# rfid_module_v4.net
KiCad netlist of a schematic drawn in EAGLE
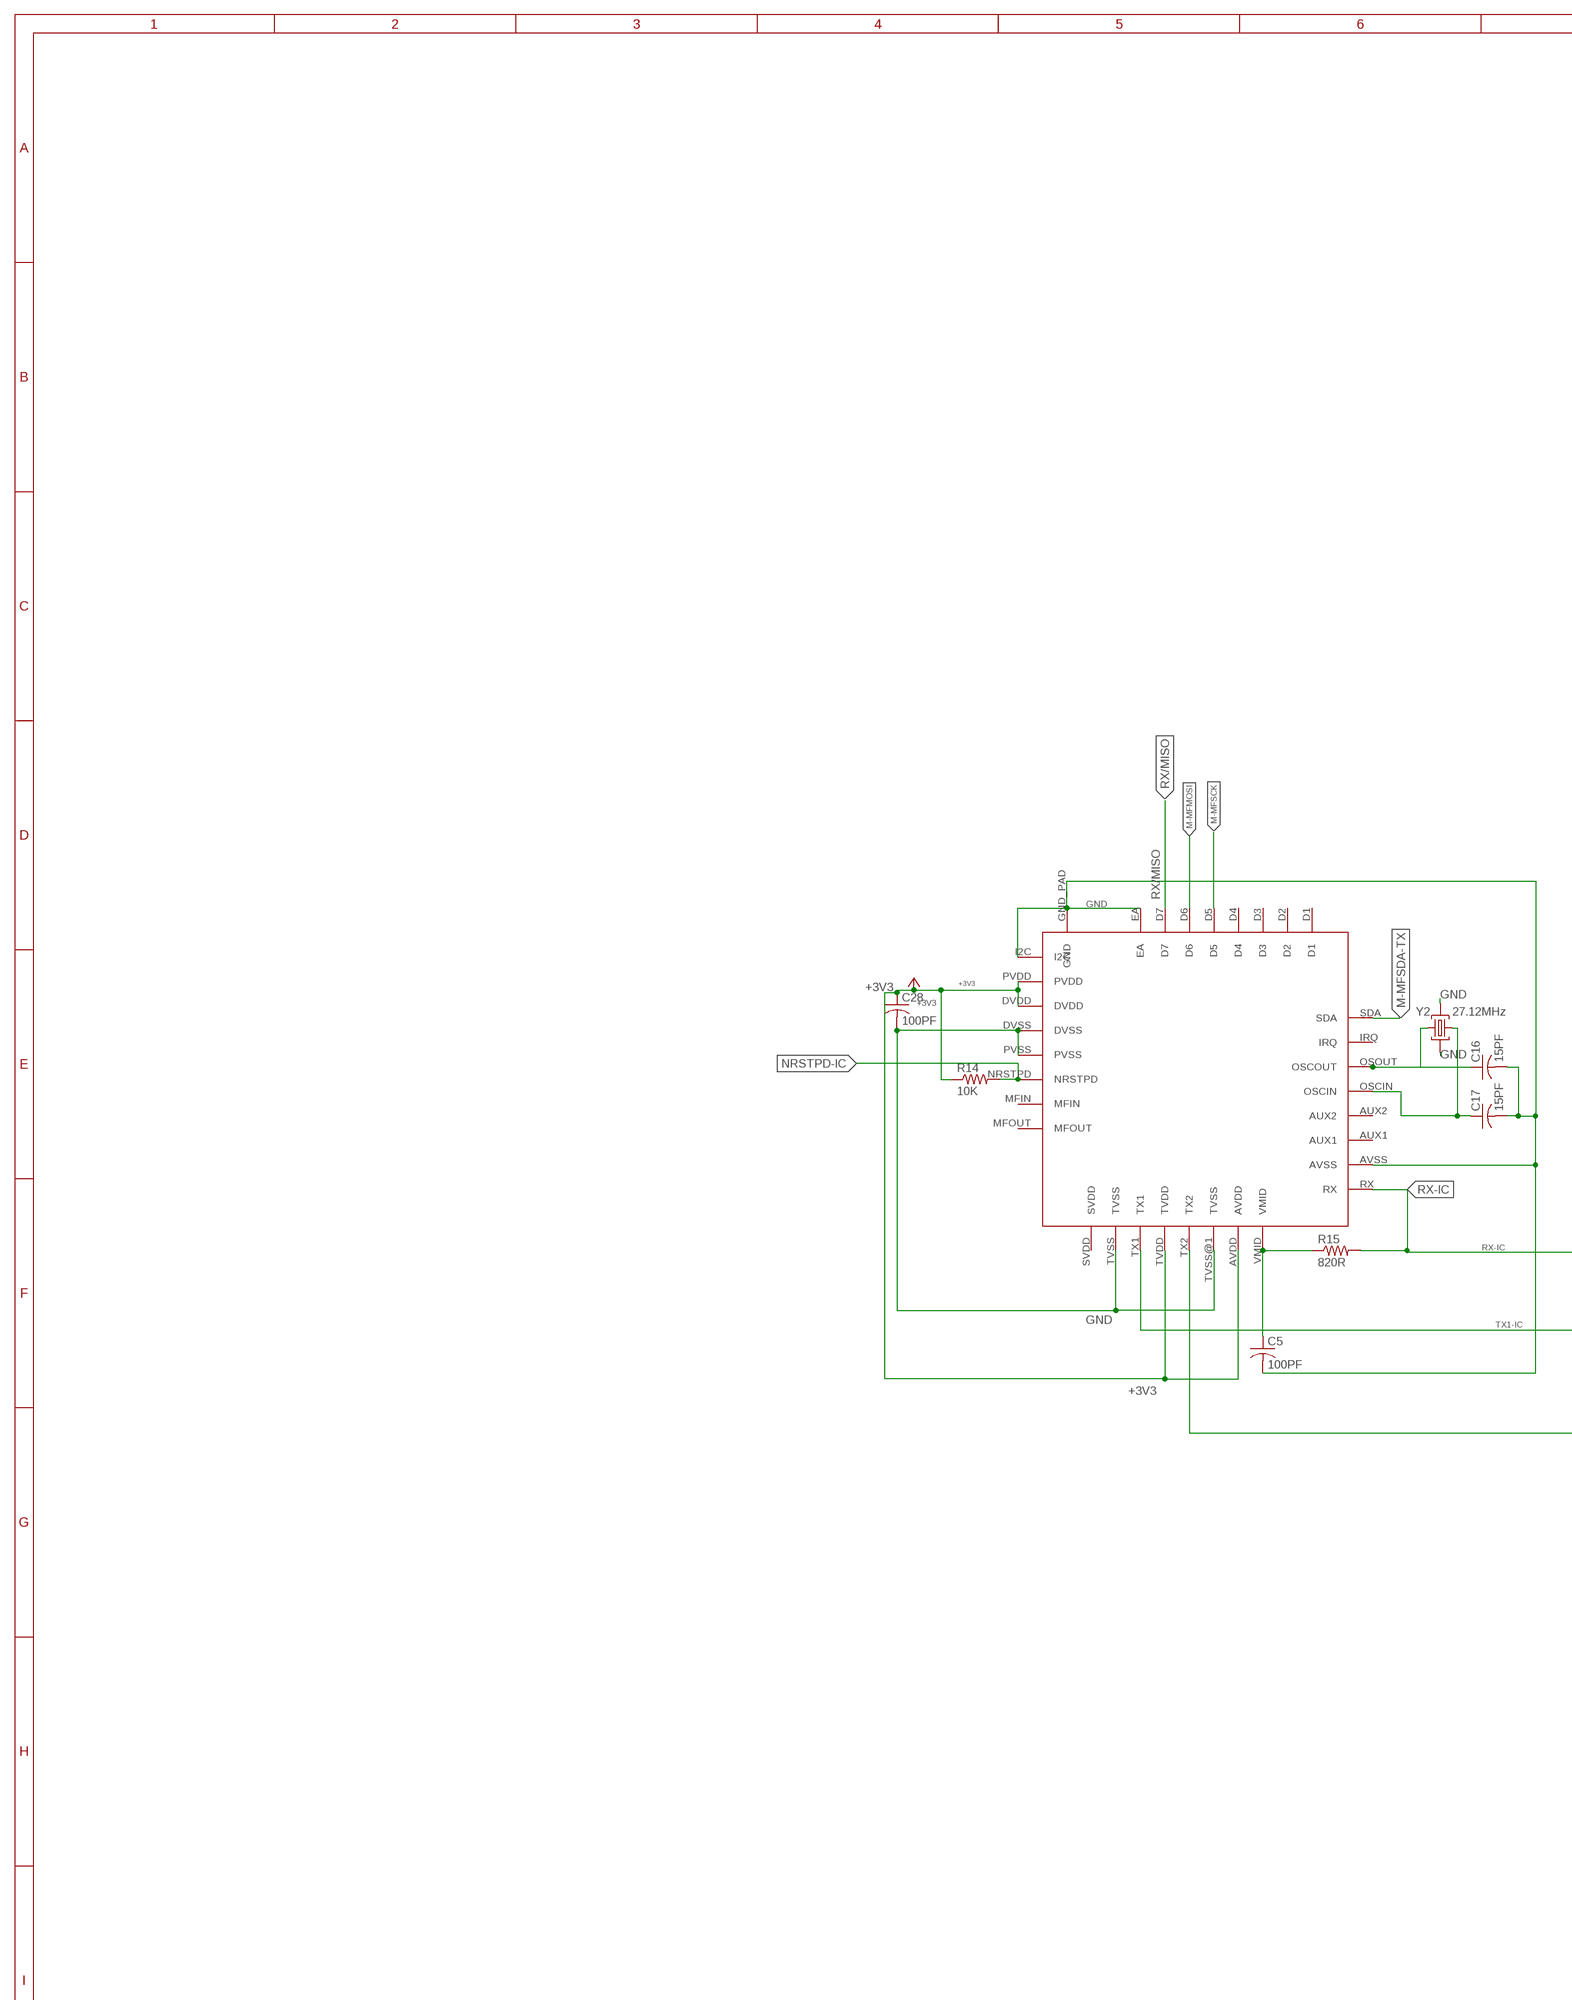
[diagram p0: schematic, sheet 1, part 1 of 2]
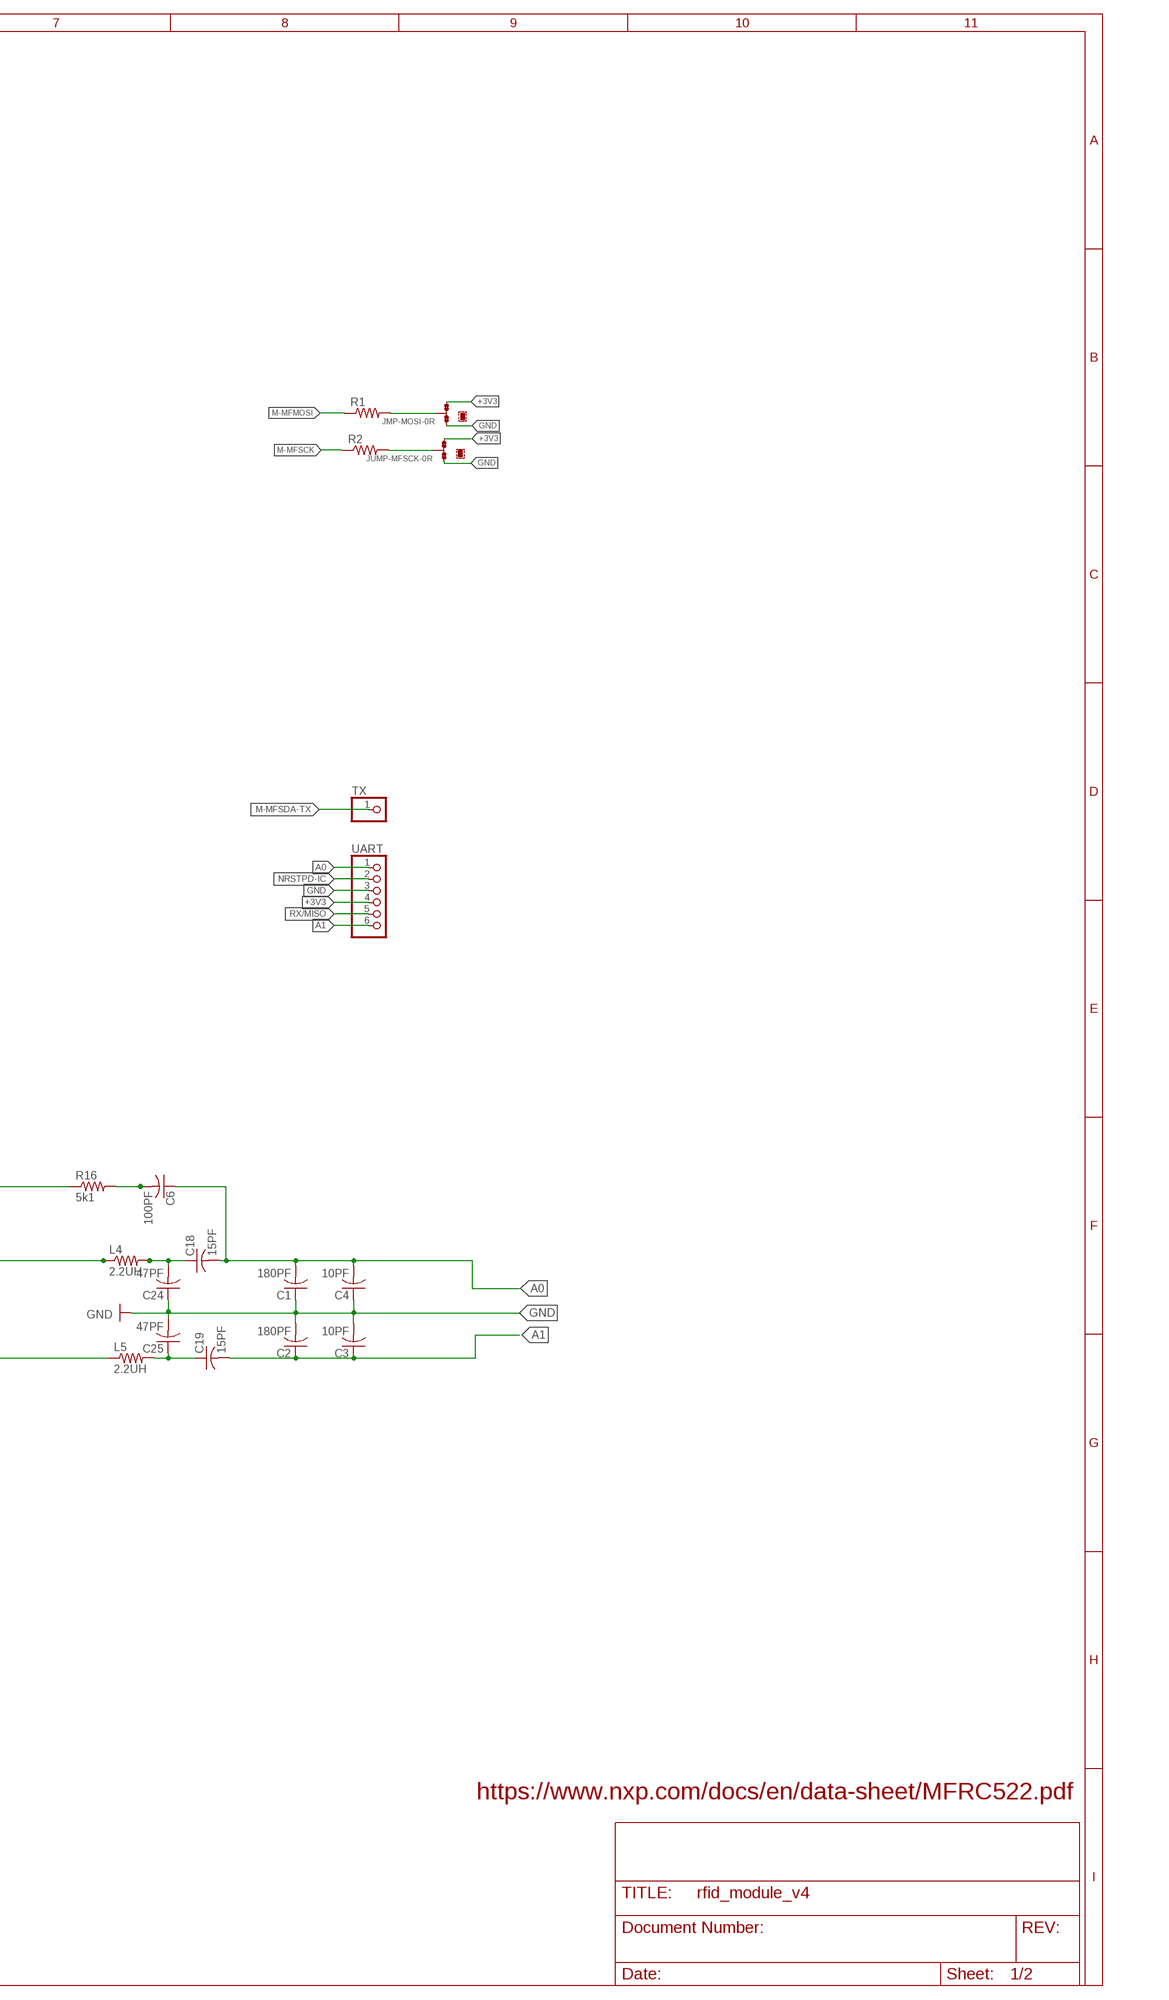
[diagram p1: schematic, sheet 1, part 2 of 2]
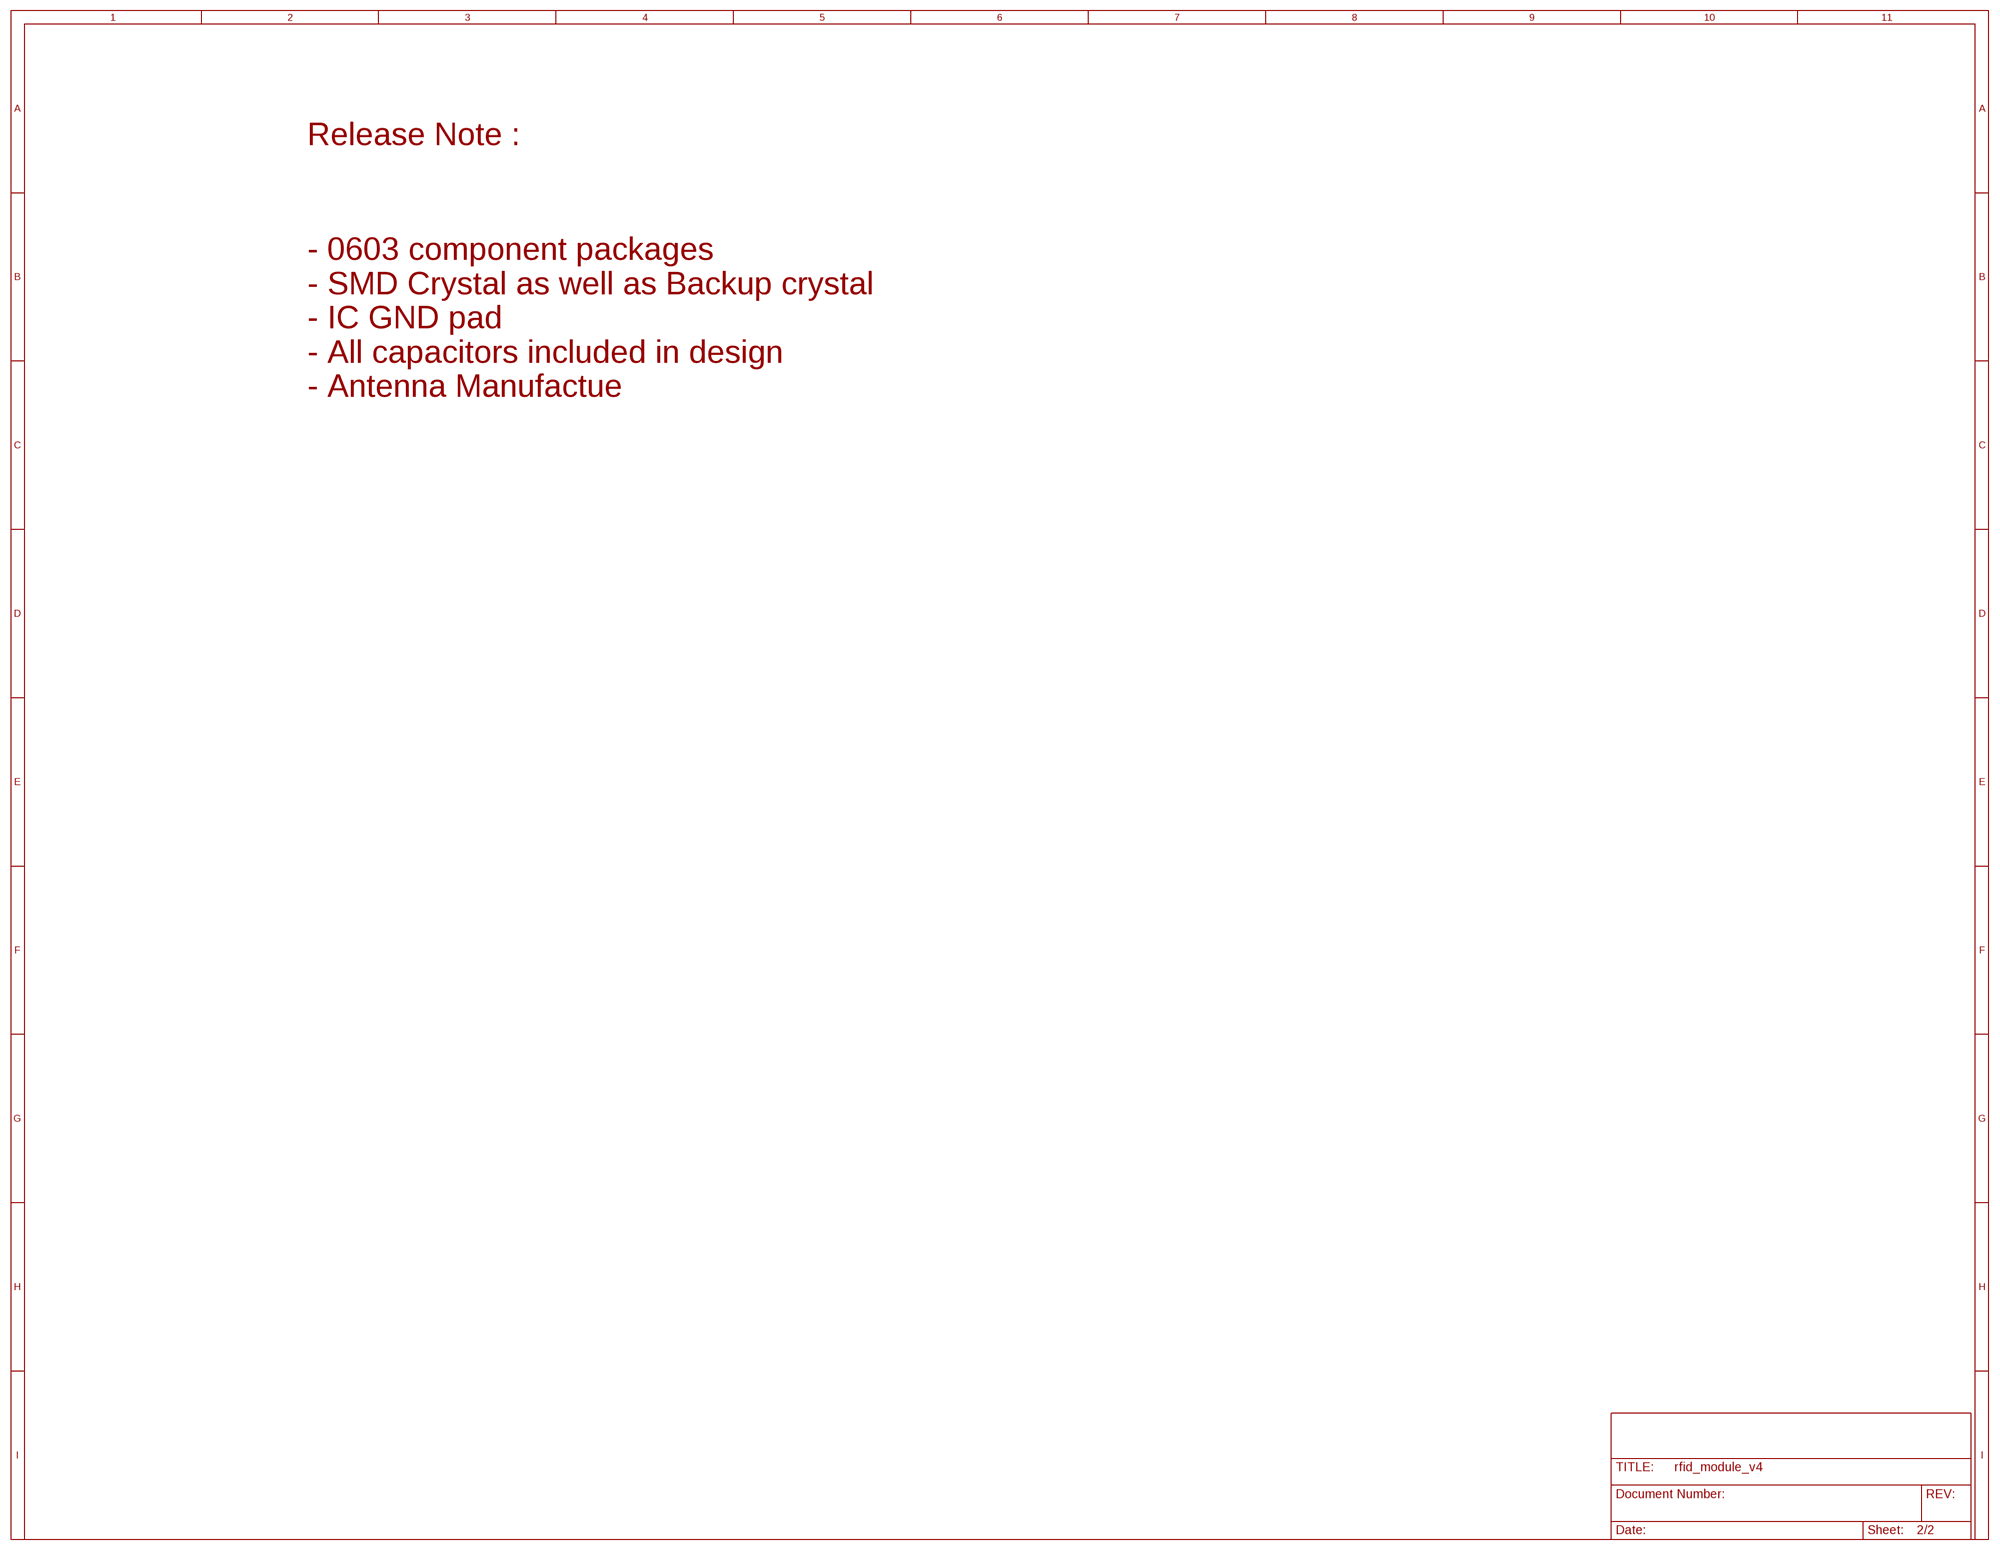
[diagram p2: schematic, sheet 2]

(export (version "E")
  (design (tool "Eeschema 10.0.6"))
  (components
    (comp (ref "C1")
      (value "180PF")
      (footprint "eagle-import:C0603")
      (libsource (lib "eagle-import") (part "C-USC0603"))
    )
    (comp (ref "C2")
      (value "180PF")
      (footprint "eagle-import:C0603")
      (libsource (lib "eagle-import") (part "C-USC0603"))
    )
    (comp (ref "C3")
      (value "10PF")
      (footprint "eagle-import:C0603")
      (libsource (lib "eagle-import") (part "C-USC0603"))
    )
    (comp (ref "C4")
      (value "10PF")
      (footprint "eagle-import:C0603")
      (libsource (lib "eagle-import") (part "C-USC0603"))
    )
    (comp (ref "C5")
      (value "100PF")
      (footprint "eagle-import:C0603")
      (libsource (lib "eagle-import") (part "C-USC0603"))
    )
    (comp (ref "C6")
      (value "100PF")
      (footprint "eagle-import:C0603")
      (libsource (lib "eagle-import") (part "C-USC0603"))
    )
    (comp (ref "C16")
      (value "15PF")
      (footprint "eagle-import:C0603")
      (libsource (lib "eagle-import") (part "C-USC0603"))
    )
    (comp (ref "C17")
      (value "15PF")
      (footprint "eagle-import:C0603")
      (libsource (lib "eagle-import") (part "C-USC0603"))
    )
    (comp (ref "C18")
      (value "15PF")
      (footprint "eagle-import:C0603")
      (libsource (lib "eagle-import") (part "C-USC0603"))
    )
    (comp (ref "C19")
      (value "15PF")
      (footprint "eagle-import:C0603")
      (libsource (lib "eagle-import") (part "C-USC0603"))
    )
    (comp (ref "C24")
      (value "47PF")
      (footprint "eagle-import:C0603")
      (libsource (lib "eagle-import") (part "C-USC0603"))
    )
    (comp (ref "C25")
      (value "47PF")
      (footprint "eagle-import:C0603")
      (libsource (lib "eagle-import") (part "C-USC0603"))
    )
    (comp (ref "C28")
      (value "100PF")
      (footprint "eagle-import:C0603")
      (libsource (lib "eagle-import") (part "C-USC0603"))
    )
    (comp (ref "JMP-MOSI")
      (value "0R-JUMPA")
      (footprint "eagle-import:A0R-JMP")
      (libsource (lib "eagle-import") (part "0R-JUMPA"))
    )
    (comp (ref "JUMP-MFSCK")
      (value "0R-JUMPA")
      (footprint "eagle-import:A0R-JMP")
      (libsource (lib "eagle-import") (part "0R-JUMPA"))
    )
    (comp (ref "L4")
      (value "2.2UH")
      (footprint "eagle-import:R0603")
      (libsource (lib "eagle-import") (part "R-US_R0603"))
    )
    (comp (ref "L5")
      (value "2.2UH")
      (footprint "eagle-import:R0603")
      (libsource (lib "eagle-import") (part "R-US_R0603"))
    )
    (comp (ref "R1")
      (value "R-US_R0603")
      (footprint "eagle-import:R0603")
      (libsource (lib "eagle-import") (part "R-US_R0603"))
    )
    (comp (ref "R2")
      (value "R-US_R0603")
      (footprint "eagle-import:R0603")
      (libsource (lib "eagle-import") (part "R-US_R0603"))
    )
    (comp (ref "R14")
      (value "10K")
      (footprint "eagle-import:R0603")
      (libsource (lib "eagle-import") (part "R-US_R0603"))
    )
    (comp (ref "R15")
      (value "820R")
      (footprint "eagle-import:R0603")
      (libsource (lib "eagle-import") (part "R-US_R0603"))
    )
    (comp (ref "R16")
      (value "5k1")
      (footprint "eagle-import:R0603")
      (libsource (lib "eagle-import") (part "R-US_R0603"))
    )
    (comp (ref "TX")
      (value "PINHD-1X1")
      (footprint "eagle-import:1X01")
      (libsource (lib "eagle-import") (part "PINHD-1X1"))
    )
    (comp (ref "U$1")
      (value "MFRC522")
      (footprint "eagle-import:MFRC522")
      (libsource (lib "eagle-import") (part "MFRC522"))
    )
    (comp (ref "UART")
      (value "PINHD-1X6")
      (footprint "eagle-import:1X06")
      (libsource (lib "eagle-import") (part "PINHD-1X6"))
    )
    (comp (ref "Y2")
      (value "27.12MHz")
      (footprint "eagle-import:CRYSTAL-3.2-2.5")
      (libsource (lib "eagle-import") (part "CRYSTAL-3.2-2.5"))
    )
  )
  (nets
    (net (code "1") (name "+3V3") (class "Default")
      (node (ref "C28") (pin "1") (pinfunction "1_1") (pintype "passive"))
      (node (ref "JMP-MOSI") (pin "3") (pinfunction "3_3") (pintype "passive"))
      (node (ref "JUMP-MFSCK") (pin "3") (pinfunction "3_3") (pintype "passive"))
      (node (ref "R14") (pin "1") (pinfunction "1_1") (pintype "passive"))
      (node (ref "U$1") (pin "AVDD") (pinfunction "AVDD_AVDD") (pintype "bidirectional"))
      (node (ref "U$1") (pin "DVDD") (pinfunction "DVDD_DVDD") (pintype "bidirectional"))
      (node (ref "U$1") (pin "PVDD") (pinfunction "PVDD_PVDD") (pintype "bidirectional"))
      (node (ref "U$1") (pin "TVDD") (pinfunction "TVDD_TVDD") (pintype "bidirectional"))
      (node (ref "UART") (pin "4") (pinfunction "4_4") (pintype "passive"))
    )
    (net (code "2") (name "A0") (class "Default")
      (node (ref "C1") (pin "2") (pinfunction "2_2") (pintype "passive"))
      (node (ref "C18") (pin "2") (pinfunction "2_2") (pintype "passive"))
      (node (ref "C4") (pin "2") (pinfunction "2_2") (pintype "passive"))
      (node (ref "C6") (pin "1") (pinfunction "1_1") (pintype "passive"))
      (node (ref "UART") (pin "1") (pinfunction "1_1") (pintype "passive"))
    )
    (net (code "3") (name "A1") (class "Default")
      (node (ref "C19") (pin "2") (pinfunction "2_2") (pintype "passive"))
      (node (ref "C2") (pin "1") (pinfunction "1_1") (pintype "passive"))
      (node (ref "C3") (pin "1") (pinfunction "1_1") (pintype "passive"))
      (node (ref "UART") (pin "6") (pinfunction "6_6") (pintype "passive"))
    )
    (net (code "4") (name "GND") (class "Default")
      (node (ref "C1") (pin "1") (pinfunction "1_1") (pintype "passive"))
      (node (ref "C16") (pin "2") (pinfunction "2_2") (pintype "passive"))
      (node (ref "C17") (pin "2") (pinfunction "2_2") (pintype "passive"))
      (node (ref "C2") (pin "2") (pinfunction "2_2") (pintype "passive"))
      (node (ref "C24") (pin "1") (pinfunction "1_1") (pintype "passive"))
      (node (ref "C25") (pin "2") (pinfunction "2_2") (pintype "passive"))
      (node (ref "C28") (pin "2") (pinfunction "2_2") (pintype "passive"))
      (node (ref "C3") (pin "2") (pinfunction "2_2") (pintype "passive"))
      (node (ref "C4") (pin "1") (pinfunction "1_1") (pintype "passive"))
      (node (ref "C5") (pin "2") (pinfunction "2_2") (pintype "passive"))
      (node (ref "JMP-MOSI") (pin "1") (pinfunction "1_1") (pintype "passive"))
      (node (ref "JUMP-MFSCK") (pin "1") (pinfunction "1_1") (pintype "passive"))
      (node (ref "U$1") (pin "AVSS") (pinfunction "AVSS_AVSS") (pintype "bidirectional"))
      (node (ref "U$1") (pin "DVSS") (pinfunction "DVSS_DVSS") (pintype "bidirectional"))
      (node (ref "U$1") (pin "EA") (pinfunction "EA_EA") (pintype "bidirectional"))
      (node (ref "U$1") (pin "GND_PAD") (pinfunction "GND_GND_PAD") (pintype "bidirectional"))
      (node (ref "U$1") (pin "I2C") (pinfunction "I2C_I2C") (pintype "bidirectional"))
      (node (ref "U$1") (pin "PVSS") (pinfunction "PVSS_PVSS") (pintype "bidirectional"))
      (node (ref "U$1") (pin "TVSS") (pinfunction "TVSS_TVSS") (pintype "bidirectional"))
      (node (ref "U$1") (pin "TVSS@1") (pinfunction "TVSS_TVSS@1") (pintype "bidirectional"))
      (node (ref "UART") (pin "3") (pinfunction "3_3") (pintype "passive"))
      (node (ref "Y2") (pin "2") (pinfunction "GND_2") (pintype "passive"))
      (node (ref "Y2") (pin "4") (pinfunction "GND_4") (pintype "passive"))
    )
    (net (code "5") (name "M-MFMOSI") (class "Default")
      (node (ref "R1") (pin "1") (pinfunction "1_1") (pintype "passive"))
      (node (ref "U$1") (pin "D6") (pinfunction "D6_D6") (pintype "bidirectional"))
    )
    (net (code "6") (name "M-MFSCK") (class "Default")
      (node (ref "R2") (pin "1") (pinfunction "1_1") (pintype "passive"))
      (node (ref "U$1") (pin "D5") (pinfunction "D5_D5") (pintype "bidirectional"))
    )
    (net (code "7") (name "M-MFSDA-TX") (class "Default")
      (node (ref "TX") (pin "1") (pinfunction "1_1") (pintype "passive"))
      (node (ref "U$1") (pin "SDA") (pinfunction "SDA_SDA") (pintype "bidirectional"))
    )
    (net (code "8") (name "NRSTPD-IC") (class "Default")
      (node (ref "R14") (pin "2") (pinfunction "2_2") (pintype "passive"))
      (node (ref "U$1") (pin "NRSTPD") (pinfunction "NRSTPD_NRSTPD") (pintype "bidirectional"))
      (node (ref "UART") (pin "2") (pinfunction "2_2") (pintype "passive"))
    )
    (net (code "9") (name "Net-(C5-Pad1)") (class "Default")
      (node (ref "C5") (pin "1") (pinfunction "1_1") (pintype "passive"))
      (node (ref "R15") (pin "1") (pinfunction "1_1") (pintype "passive"))
      (node (ref "U$1") (pin "VMID") (pinfunction "VMID_VMID") (pintype "bidirectional"))
    )
    (net (code "10") (name "Net-(C6-Pad2)") (class "Default")
      (node (ref "C6") (pin "2") (pinfunction "2_2") (pintype "passive"))
      (node (ref "R16") (pin "2") (pinfunction "2_2") (pintype "passive"))
    )
    (net (code "11") (name "Net-(C18-Pad1)") (class "Default")
      (node (ref "C18") (pin "1") (pinfunction "1_1") (pintype "passive"))
      (node (ref "C24") (pin "2") (pinfunction "2_2") (pintype "passive"))
      (node (ref "L4") (pin "2") (pinfunction "2_2") (pintype "passive"))
    )
    (net (code "12") (name "Net-(C19-Pad1)") (class "Default")
      (node (ref "C19") (pin "1") (pinfunction "1_1") (pintype "passive"))
      (node (ref "C25") (pin "1") (pinfunction "1_1") (pintype "passive"))
      (node (ref "L5") (pin "2") (pinfunction "2_2") (pintype "passive"))
    )
    (net (code "13") (name "Net-(JMP-MOSI-Pad2)") (class "Default")
      (node (ref "JMP-MOSI") (pin "2") (pinfunction "2_2") (pintype "passive"))
      (node (ref "R1") (pin "2") (pinfunction "2_2") (pintype "passive"))
    )
    (net (code "14") (name "Net-(JUMP-MFSCK-Pad2)") (class "Default")
      (node (ref "JUMP-MFSCK") (pin "2") (pinfunction "2_2") (pintype "passive"))
      (node (ref "R2") (pin "2") (pinfunction "2_2") (pintype "passive"))
    )
    (net (code "15") (name "Net-(L5-Pad1)") (class "Default")
      (node (ref "L5") (pin "1") (pinfunction "1_1") (pintype "passive"))
      (node (ref "U$1") (pin "TX2") (pinfunction "TX2_TX2") (pintype "bidirectional"))
    )
    (net (code "16") (name "Net-(U$1-OSCOUT)") (class "Default")
      (node (ref "C16") (pin "1") (pinfunction "1_1") (pintype "passive"))
      (node (ref "U$1") (pin "OSOUT") (pinfunction "OSCOUT_OSOUT") (pintype "bidirectional"))
      (node (ref "Y2") (pin "3") (pinfunction "C2_3") (pintype "passive"))
    )
    (net (code "17") (name "Net-(Y2-C1)") (class "Default")
      (node (ref "C17") (pin "1") (pinfunction "1_1") (pintype "passive"))
      (node (ref "U$1") (pin "OSCIN") (pinfunction "OSCIN_OSCIN") (pintype "bidirectional"))
      (node (ref "Y2") (pin "1") (pinfunction "C1_1") (pintype "passive"))
    )
    (net (code "18") (name "RX-IC") (class "Default")
      (node (ref "R15") (pin "2") (pinfunction "2_2") (pintype "passive"))
      (node (ref "R16") (pin "1") (pinfunction "1_1") (pintype "passive"))
      (node (ref "U$1") (pin "RX") (pinfunction "RX_RX") (pintype "bidirectional"))
    )
    (net (code "19") (name "RX{slash}MISO") (class "Default")
      (node (ref "U$1") (pin "D7") (pinfunction "D7_D7") (pintype "bidirectional"))
      (node (ref "UART") (pin "5") (pinfunction "5_5") (pintype "passive"))
    )
    (net (code "20") (name "TX1-IC") (class "Default")
      (node (ref "L4") (pin "1") (pinfunction "1_1") (pintype "passive"))
      (node (ref "U$1") (pin "TX1") (pinfunction "TX1_TX1") (pintype "bidirectional"))
    )
    (net (code "21") (name "unconnected-(U$1-PadAUX1)") (class "Default")
      (node (ref "U$1") (pin "AUX1") (pinfunction "AUX1_AUX1") (pintype "bidirectional"))
    )
    (net (code "22") (name "unconnected-(U$1-PadAUX2)") (class "Default")
      (node (ref "U$1") (pin "AUX2") (pinfunction "AUX2_AUX2") (pintype "bidirectional"))
    )
    (net (code "23") (name "unconnected-(U$1-PadD1)") (class "Default")
      (node (ref "U$1") (pin "D1") (pinfunction "D1_D1") (pintype "bidirectional"))
    )
    (net (code "24") (name "unconnected-(U$1-PadD2)") (class "Default")
      (node (ref "U$1") (pin "D2") (pinfunction "D2_D2") (pintype "bidirectional"))
    )
    (net (code "25") (name "unconnected-(U$1-PadD3)") (class "Default")
      (node (ref "U$1") (pin "D3") (pinfunction "D3_D3") (pintype "bidirectional"))
    )
    (net (code "26") (name "unconnected-(U$1-PadD4)") (class "Default")
      (node (ref "U$1") (pin "D4") (pinfunction "D4_D4") (pintype "bidirectional"))
    )
    (net (code "27") (name "unconnected-(U$1-PadIRQ)") (class "Default")
      (node (ref "U$1") (pin "IRQ") (pinfunction "IRQ_IRQ") (pintype "bidirectional"))
    )
    (net (code "28") (name "unconnected-(U$1-PadMFIN)") (class "Default")
      (node (ref "U$1") (pin "MFIN") (pinfunction "MFIN_MFIN") (pintype "bidirectional"))
    )
    (net (code "29") (name "unconnected-(U$1-PadMFOUT)") (class "Default")
      (node (ref "U$1") (pin "MFOUT") (pinfunction "MFOUT_MFOUT") (pintype "bidirectional"))
    )
    (net (code "30") (name "unconnected-(U$1-PadSVDD)") (class "Default")
      (node (ref "U$1") (pin "SVDD") (pinfunction "SVDD_SVDD") (pintype "bidirectional"))
    )
  )
)
